# smartsensorRevB.net
KiCad netlist of a schematic drawn in EAGLE
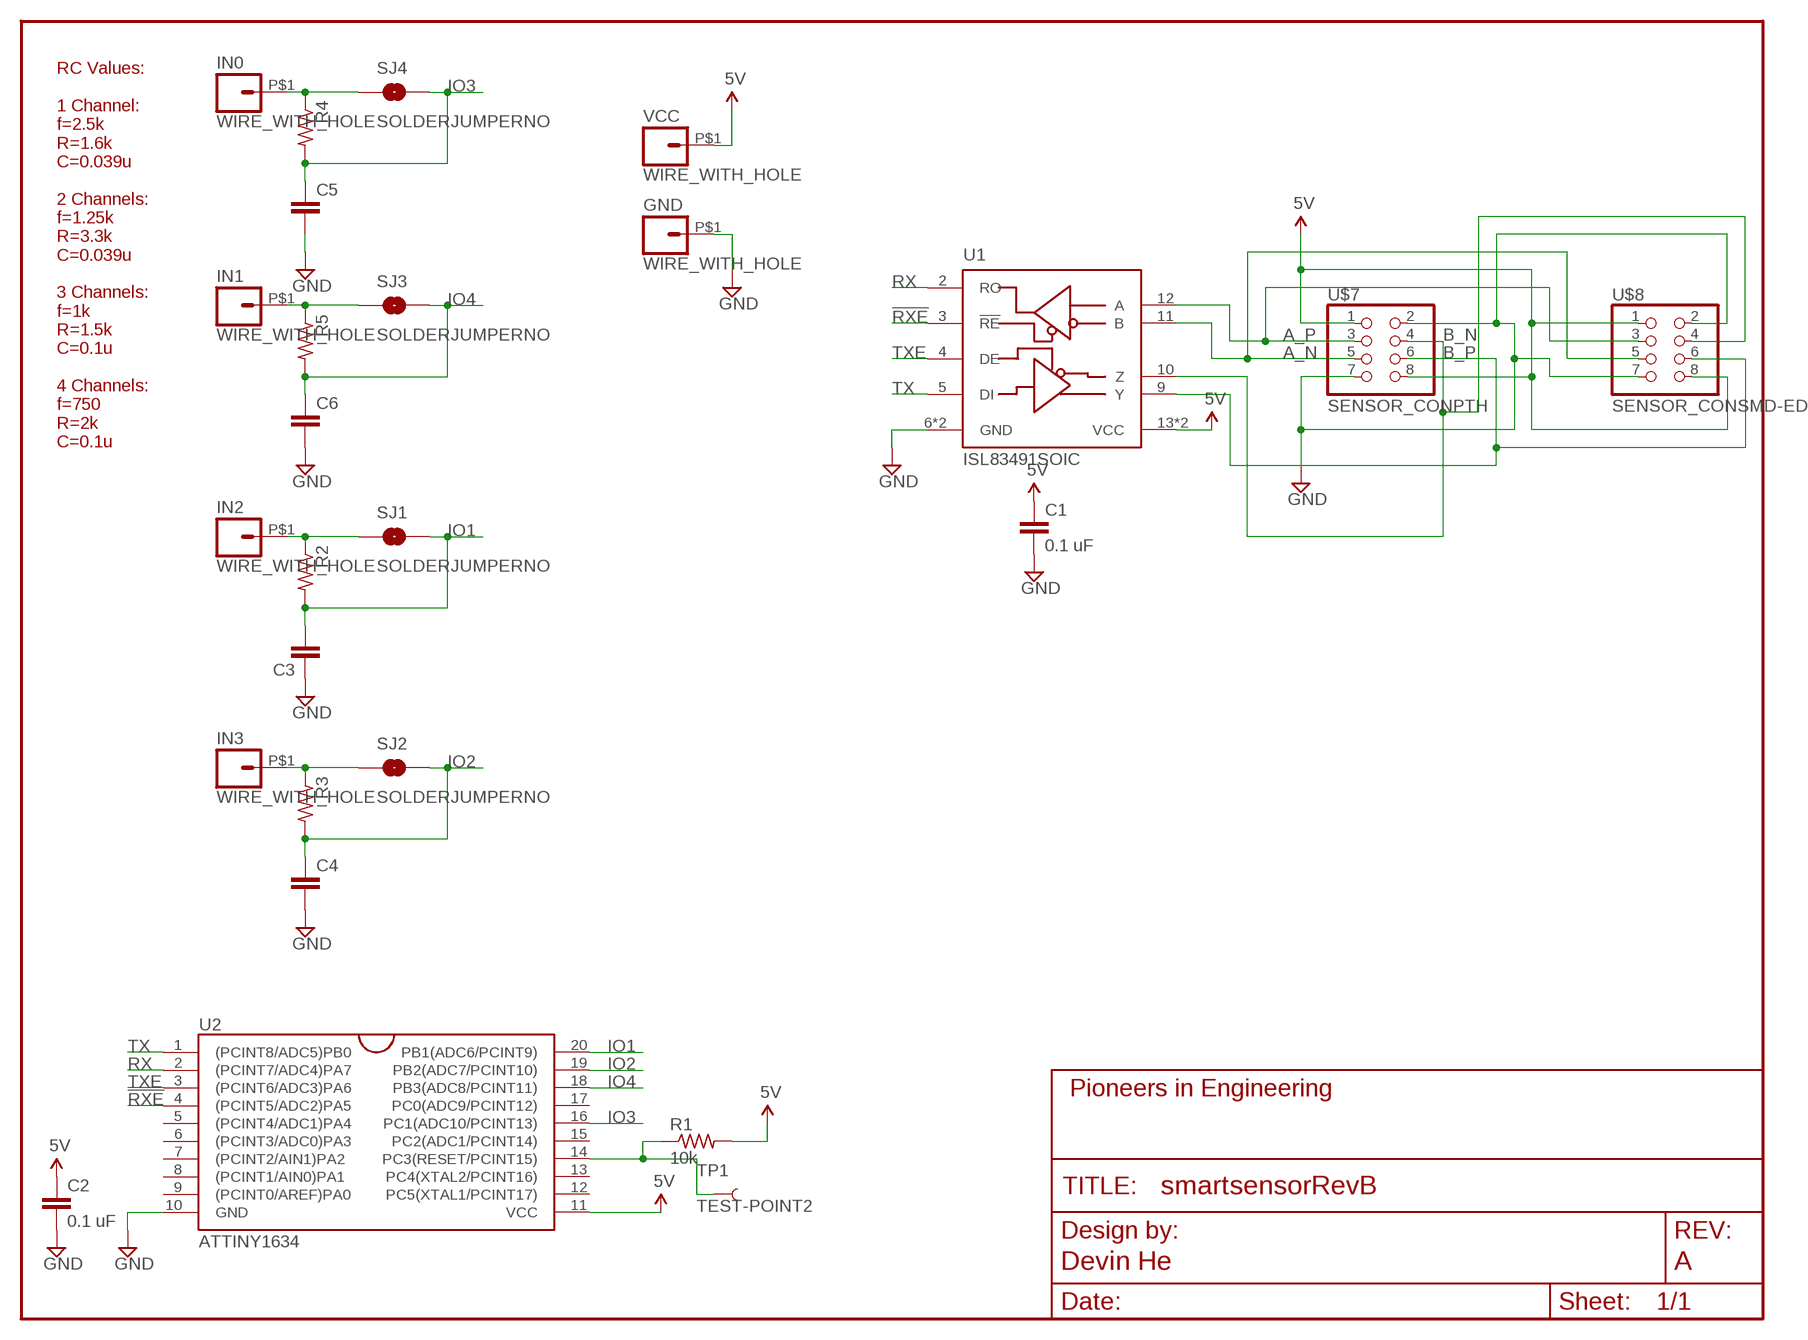
[diagram p0: schematic, sheet 1]

(export (version "E")
  (design (tool "Eeschema 10.0.6"))
  (components
    (comp (ref "C1")
      (value "0.1 uF")
      (footprint "eagle-import:0603-CAP")
      (libsource (lib "eagle-import") (part "CAP0603-CAP"))
    )
    (comp (ref "C2")
      (value "0.1 uF")
      (footprint "eagle-import:0603-CAP")
      (libsource (lib "eagle-import") (part "CAP0603-CAP"))
    )
    (comp (ref "C3")
      (value "CAP0603-CAP")
      (footprint "eagle-import:0603-CAP")
      (libsource (lib "eagle-import") (part "CAP0603-CAP"))
    )
    (comp (ref "C4")
      (value "CAP0603-CAP")
      (footprint "eagle-import:0603-CAP")
      (libsource (lib "eagle-import") (part "CAP0603-CAP"))
    )
    (comp (ref "C5")
      (value "CAP0603-CAP")
      (footprint "eagle-import:0603-CAP")
      (libsource (lib "eagle-import") (part "CAP0603-CAP"))
    )
    (comp (ref "C6")
      (value "CAP0603-CAP")
      (footprint "eagle-import:0603-CAP")
      (libsource (lib "eagle-import") (part "CAP0603-CAP"))
    )
    (comp (ref "GND")
      (value "WIRE_WITH_HOLE")
      (footprint "eagle-import:WIRE_WITH_HOLE")
      (libsource (lib "eagle-import") (part "WIRE_WITH_HOLE"))
    )
    (comp (ref "IN0")
      (value "WIRE_WITH_HOLE")
      (footprint "eagle-import:WIRE_WITH_HOLE")
      (libsource (lib "eagle-import") (part "WIRE_WITH_HOLE"))
    )
    (comp (ref "IN1")
      (value "WIRE_WITH_HOLE")
      (footprint "eagle-import:WIRE_WITH_HOLE")
      (libsource (lib "eagle-import") (part "WIRE_WITH_HOLE"))
    )
    (comp (ref "IN2")
      (value "WIRE_WITH_HOLE")
      (footprint "eagle-import:WIRE_WITH_HOLE")
      (libsource (lib "eagle-import") (part "WIRE_WITH_HOLE"))
    )
    (comp (ref "IN3")
      (value "WIRE_WITH_HOLE")
      (footprint "eagle-import:WIRE_WITH_HOLE")
      (libsource (lib "eagle-import") (part "WIRE_WITH_HOLE"))
    )
    (comp (ref "R1")
      (value "10k")
      (footprint "eagle-import:R0603")
      (libsource (lib "eagle-import") (part "R-US_R0603"))
    )
    (comp (ref "R2")
      (value "R-US_R0603")
      (footprint "eagle-import:R0603")
      (libsource (lib "eagle-import") (part "R-US_R0603"))
    )
    (comp (ref "R3")
      (value "R-US_R0603")
      (footprint "eagle-import:R0603")
      (libsource (lib "eagle-import") (part "R-US_R0603"))
    )
    (comp (ref "R4")
      (value "R-US_R0603")
      (footprint "eagle-import:R0603")
      (libsource (lib "eagle-import") (part "R-US_R0603"))
    )
    (comp (ref "R5")
      (value "R-US_R0603")
      (footprint "eagle-import:R0603")
      (libsource (lib "eagle-import") (part "R-US_R0603"))
    )
    (comp (ref "SJ1")
      (value "SOLDERJUMPERNO")
      (footprint "eagle-import:SJ_2S-NO")
      (libsource (lib "eagle-import") (part "SOLDERJUMPERNO"))
    )
    (comp (ref "SJ2")
      (value "SOLDERJUMPERNO")
      (footprint "eagle-import:SJ_2S-NO")
      (libsource (lib "eagle-import") (part "SOLDERJUMPERNO"))
    )
    (comp (ref "SJ3")
      (value "SOLDERJUMPERNO")
      (footprint "eagle-import:SJ_2S-NO")
      (libsource (lib "eagle-import") (part "SOLDERJUMPERNO"))
    )
    (comp (ref "SJ4")
      (value "SOLDERJUMPERNO")
      (footprint "eagle-import:SJ_2S-NO")
      (libsource (lib "eagle-import") (part "SOLDERJUMPERNO"))
    )
    (comp (ref "TP1")
      (value "TEST-POINT2")
      (footprint "eagle-import:PAD.02X.02")
      (libsource (lib "eagle-import") (part "TEST-POINT2"))
    )
    (comp (ref "U$7")
      (value "SENSOR_CONPTH")
      (footprint "eagle-import:2X4")
      (libsource (lib "eagle-import") (part "SENSOR_CONPTH"))
    )
    (comp (ref "U$8")
      (value "SENSOR_CONSMD-EDGE")
      (footprint "eagle-import:2X4-EDGE")
      (libsource (lib "eagle-import") (part "SENSOR_CONSMD-EDGE"))
    )
    (comp (ref "U1")
      (value "ISL83491SOIC")
      (footprint "eagle-import:SOIC14")
      (libsource (lib "eagle-import") (part "ISL83491SOIC"))
    )
    (comp (ref "U2")
      (value "ATTINY1634")
      (footprint "eagle-import:SOIC20S")
      (libsource (lib "eagle-import") (part "ATTINY1634"))
    )
    (comp (ref "VCC")
      (value "WIRE_WITH_HOLE")
      (footprint "eagle-import:WIRE_WITH_HOLE")
      (libsource (lib "eagle-import") (part "WIRE_WITH_HOLE"))
    )
  )
  (nets
    (net (code "1") (name "/A_N") (class "Default")
      (node (ref "U$7") (pin "5") (pinfunction "5_5") (pintype "passive"))
      (node (ref "U$8") (pin "5") (pinfunction "5_5") (pintype "passive"))
      (node (ref "U1") (pin "11") (pinfunction "B_11") (pintype "bidirectional"))
    )
    (net (code "2") (name "/A_P") (class "Default")
      (node (ref "U$7") (pin "3") (pinfunction "3_3") (pintype "passive"))
      (node (ref "U$8") (pin "3") (pinfunction "3_3") (pintype "passive"))
      (node (ref "U1") (pin "12") (pinfunction "A_12") (pintype "bidirectional"))
    )
    (net (code "3") (name "/B_N") (class "Default")
      (node (ref "U$7") (pin "4") (pinfunction "4_4") (pintype "passive"))
      (node (ref "U$8") (pin "4") (pinfunction "4_4") (pintype "passive"))
      (node (ref "U1") (pin "10") (pinfunction "Z_10") (pintype "bidirectional"))
    )
    (net (code "4") (name "/B_P") (class "Default")
      (node (ref "U$7") (pin "6") (pinfunction "6_6") (pintype "passive"))
      (node (ref "U$8") (pin "6") (pinfunction "6_6") (pintype "passive"))
      (node (ref "U1") (pin "9") (pinfunction "Y_9") (pintype "bidirectional"))
    )
    (net (code "5") (name "/IO1") (class "Default")
      (node (ref "C3") (pin "2") (pinfunction "2_2") (pintype "passive"))
      (node (ref "R2") (pin "2") (pinfunction "2_2") (pintype "passive"))
      (node (ref "SJ1") (pin "2") (pinfunction "2_2") (pintype "passive"))
      (node (ref "U2") (pin "20") (pinfunction "PB1(ADC6/PCINT9)_20") (pintype "bidirectional"))
    )
    (net (code "6") (name "/IO2") (class "Default")
      (node (ref "C4") (pin "1") (pinfunction "1_1") (pintype "passive"))
      (node (ref "R3") (pin "2") (pinfunction "2_2") (pintype "passive"))
      (node (ref "SJ2") (pin "2") (pinfunction "2_2") (pintype "passive"))
      (node (ref "U2") (pin "19") (pinfunction "PB2(ADC7/PCINT10)_19") (pintype "bidirectional"))
    )
    (net (code "7") (name "/IO3") (class "Default")
      (node (ref "C5") (pin "1") (pinfunction "1_1") (pintype "passive"))
      (node (ref "R4") (pin "2") (pinfunction "2_2") (pintype "passive"))
      (node (ref "SJ4") (pin "2") (pinfunction "2_2") (pintype "passive"))
      (node (ref "U2") (pin "16") (pinfunction "PC1(ADC10/PCINT13)_16") (pintype "bidirectional"))
    )
    (net (code "8") (name "/IO4") (class "Default")
      (node (ref "C6") (pin "1") (pinfunction "1_1") (pintype "passive"))
      (node (ref "R5") (pin "2") (pinfunction "2_2") (pintype "passive"))
      (node (ref "SJ3") (pin "2") (pinfunction "2_2") (pintype "passive"))
      (node (ref "U2") (pin "18") (pinfunction "PB3(ADC8/PCINT11)_18") (pintype "bidirectional"))
    )
    (net (code "9") (name "/RX") (class "Default")
      (node (ref "U1") (pin "2") (pinfunction "RO_2") (pintype "bidirectional"))
      (node (ref "U2") (pin "2") (pinfunction "(PCINT7/ADC4)PA7_2") (pintype "bidirectional"))
    )
    (net (code "10") (name "/TX") (class "Default")
      (node (ref "U1") (pin "5") (pinfunction "DI_5") (pintype "bidirectional"))
      (node (ref "U2") (pin "1") (pinfunction "(PCINT8/ADC5)PB0_1") (pintype "bidirectional"))
    )
    (net (code "11") (name "/TXE") (class "Default")
      (node (ref "U1") (pin "4") (pinfunction "DE_4") (pintype "bidirectional"))
      (node (ref "U2") (pin "3") (pinfunction "(PCINT6/ADC3)PA6_3") (pintype "bidirectional"))
    )
    (net (code "12") (name "/~{RXE}") (class "Default")
      (node (ref "U1") (pin "3") (pinfunction "~{RE}_3") (pintype "bidirectional"))
      (node (ref "U2") (pin "4") (pinfunction "(PCINT5/ADC2)PA5_4") (pintype "bidirectional"))
    )
    (net (code "13") (name "5V") (class "Default")
      (node (ref "C1") (pin "1") (pinfunction "1_1") (pintype "passive"))
      (node (ref "C2") (pin "1") (pinfunction "1_1") (pintype "passive"))
      (node (ref "R1") (pin "2") (pinfunction "2_2") (pintype "passive"))
      (node (ref "U$7") (pin "1") (pinfunction "1_1") (pintype "passive"))
      (node (ref "U$7") (pin "8") (pinfunction "8_8") (pintype "passive"))
      (node (ref "U$8") (pin "1") (pinfunction "1_1") (pintype "passive"))
      (node (ref "U$8") (pin "8") (pinfunction "8_8") (pintype "passive"))
      (node (ref "U1") (pin "13") (pinfunction "VCC_13") (pintype "bidirectional"))
      (node (ref "U1") (pin "14") (pinfunction "VCC_14") (pintype "bidirectional"))
      (node (ref "U2") (pin "11") (pinfunction "VCC_11") (pintype "bidirectional"))
      (node (ref "VCC") (pin "P$1") (pinfunction "2_P$1") (pintype "passive"))
    )
    (net (code "14") (name "GND") (class "Default")
      (node (ref "C1") (pin "2") (pinfunction "2_2") (pintype "passive"))
      (node (ref "C2") (pin "2") (pinfunction "2_2") (pintype "passive"))
      (node (ref "C3") (pin "1") (pinfunction "1_1") (pintype "passive"))
      (node (ref "C4") (pin "2") (pinfunction "2_2") (pintype "passive"))
      (node (ref "C5") (pin "2") (pinfunction "2_2") (pintype "passive"))
      (node (ref "C6") (pin "2") (pinfunction "2_2") (pintype "passive"))
      (node (ref "GND") (pin "P$1") (pinfunction "2_P$1") (pintype "passive"))
      (node (ref "U$7") (pin "2") (pinfunction "2_2") (pintype "passive"))
      (node (ref "U$7") (pin "7") (pinfunction "7_7") (pintype "passive"))
      (node (ref "U$8") (pin "2") (pinfunction "2_2") (pintype "passive"))
      (node (ref "U$8") (pin "7") (pinfunction "7_7") (pintype "passive"))
      (node (ref "U1") (pin "6") (pinfunction "GND_6") (pintype "bidirectional"))
      (node (ref "U1") (pin "7") (pinfunction "GND_7") (pintype "bidirectional"))
      (node (ref "U2") (pin "10") (pinfunction "GND_10") (pintype "bidirectional"))
    )
    (net (code "15") (name "Net-(IN0-2)") (class "Default")
      (node (ref "IN0") (pin "P$1") (pinfunction "2_P$1") (pintype "passive"))
      (node (ref "R4") (pin "1") (pinfunction "1_1") (pintype "passive"))
      (node (ref "SJ4") (pin "1") (pinfunction "1_1") (pintype "passive"))
    )
    (net (code "16") (name "Net-(IN1-2)") (class "Default")
      (node (ref "IN1") (pin "P$1") (pinfunction "2_P$1") (pintype "passive"))
      (node (ref "R5") (pin "1") (pinfunction "1_1") (pintype "passive"))
      (node (ref "SJ3") (pin "1") (pinfunction "1_1") (pintype "passive"))
    )
    (net (code "17") (name "Net-(IN2-2)") (class "Default")
      (node (ref "IN2") (pin "P$1") (pinfunction "2_P$1") (pintype "passive"))
      (node (ref "R2") (pin "1") (pinfunction "1_1") (pintype "passive"))
      (node (ref "SJ1") (pin "1") (pinfunction "1_1") (pintype "passive"))
    )
    (net (code "18") (name "Net-(IN3-2)") (class "Default")
      (node (ref "IN3") (pin "P$1") (pinfunction "2_P$1") (pintype "passive"))
      (node (ref "R3") (pin "1") (pinfunction "1_1") (pintype "passive"))
      (node (ref "SJ2") (pin "1") (pinfunction "1_1") (pintype "passive"))
    )
    (net (code "19") (name "Net-(TP1-1)") (class "Default")
      (node (ref "R1") (pin "1") (pinfunction "1_1") (pintype "passive"))
      (node (ref "TP1") (pin "P$1") (pinfunction "1_P$1") (pintype "bidirectional"))
      (node (ref "U2") (pin "14") (pinfunction "PC3(RESET/PCINT15)_14") (pintype "bidirectional"))
    )
    (net (code "20") (name "unconnected-(U2-(PCINT0{slash}AREF)PA0-Pad9)") (class "Default")
      (node (ref "U2") (pin "9") (pinfunction "(PCINT0/AREF)PA0_9") (pintype "bidirectional"))
    )
    (net (code "21") (name "unconnected-(U2-(PCINT1{slash}AIN0)PA1-Pad8)") (class "Default")
      (node (ref "U2") (pin "8") (pinfunction "(PCINT1/AIN0)PA1_8") (pintype "bidirectional"))
    )
    (net (code "22") (name "unconnected-(U2-(PCINT2{slash}AIN1)PA2-Pad7)") (class "Default")
      (node (ref "U2") (pin "7") (pinfunction "(PCINT2/AIN1)PA2_7") (pintype "bidirectional"))
    )
    (net (code "23") (name "unconnected-(U2-(PCINT3{slash}ADC0)PA3-Pad6)") (class "Default")
      (node (ref "U2") (pin "6") (pinfunction "(PCINT3/ADC0)PA3_6") (pintype "bidirectional"))
    )
    (net (code "24") (name "unconnected-(U2-(PCINT4{slash}ADC1)PA4-Pad5)") (class "Default")
      (node (ref "U2") (pin "5") (pinfunction "(PCINT4/ADC1)PA4_5") (pintype "bidirectional"))
    )
    (net (code "25") (name "unconnected-(U2-PC0(ADC9{slash}PCINT12)-Pad17)") (class "Default")
      (node (ref "U2") (pin "17") (pinfunction "PC0(ADC9/PCINT12)_17") (pintype "bidirectional"))
    )
    (net (code "26") (name "unconnected-(U2-PC2(ADC1{slash}PCINT14)-Pad15)") (class "Default")
      (node (ref "U2") (pin "15") (pinfunction "PC2(ADC1/PCINT14)_15") (pintype "bidirectional"))
    )
    (net (code "27") (name "unconnected-(U2-PC4(XTAL2{slash}PCINT16)-Pad13)") (class "Default")
      (node (ref "U2") (pin "13") (pinfunction "PC4(XTAL2/PCINT16)_13") (pintype "bidirectional"))
    )
    (net (code "28") (name "unconnected-(U2-PC5(XTAL1{slash}PCINT17)-Pad12)") (class "Default")
      (node (ref "U2") (pin "12") (pinfunction "PC5(XTAL1/PCINT17)_12") (pintype "bidirectional"))
    )
  )
)
